# JTAG_Configuration.net
KiCad netlist of a schematic drawn in Altium Designer
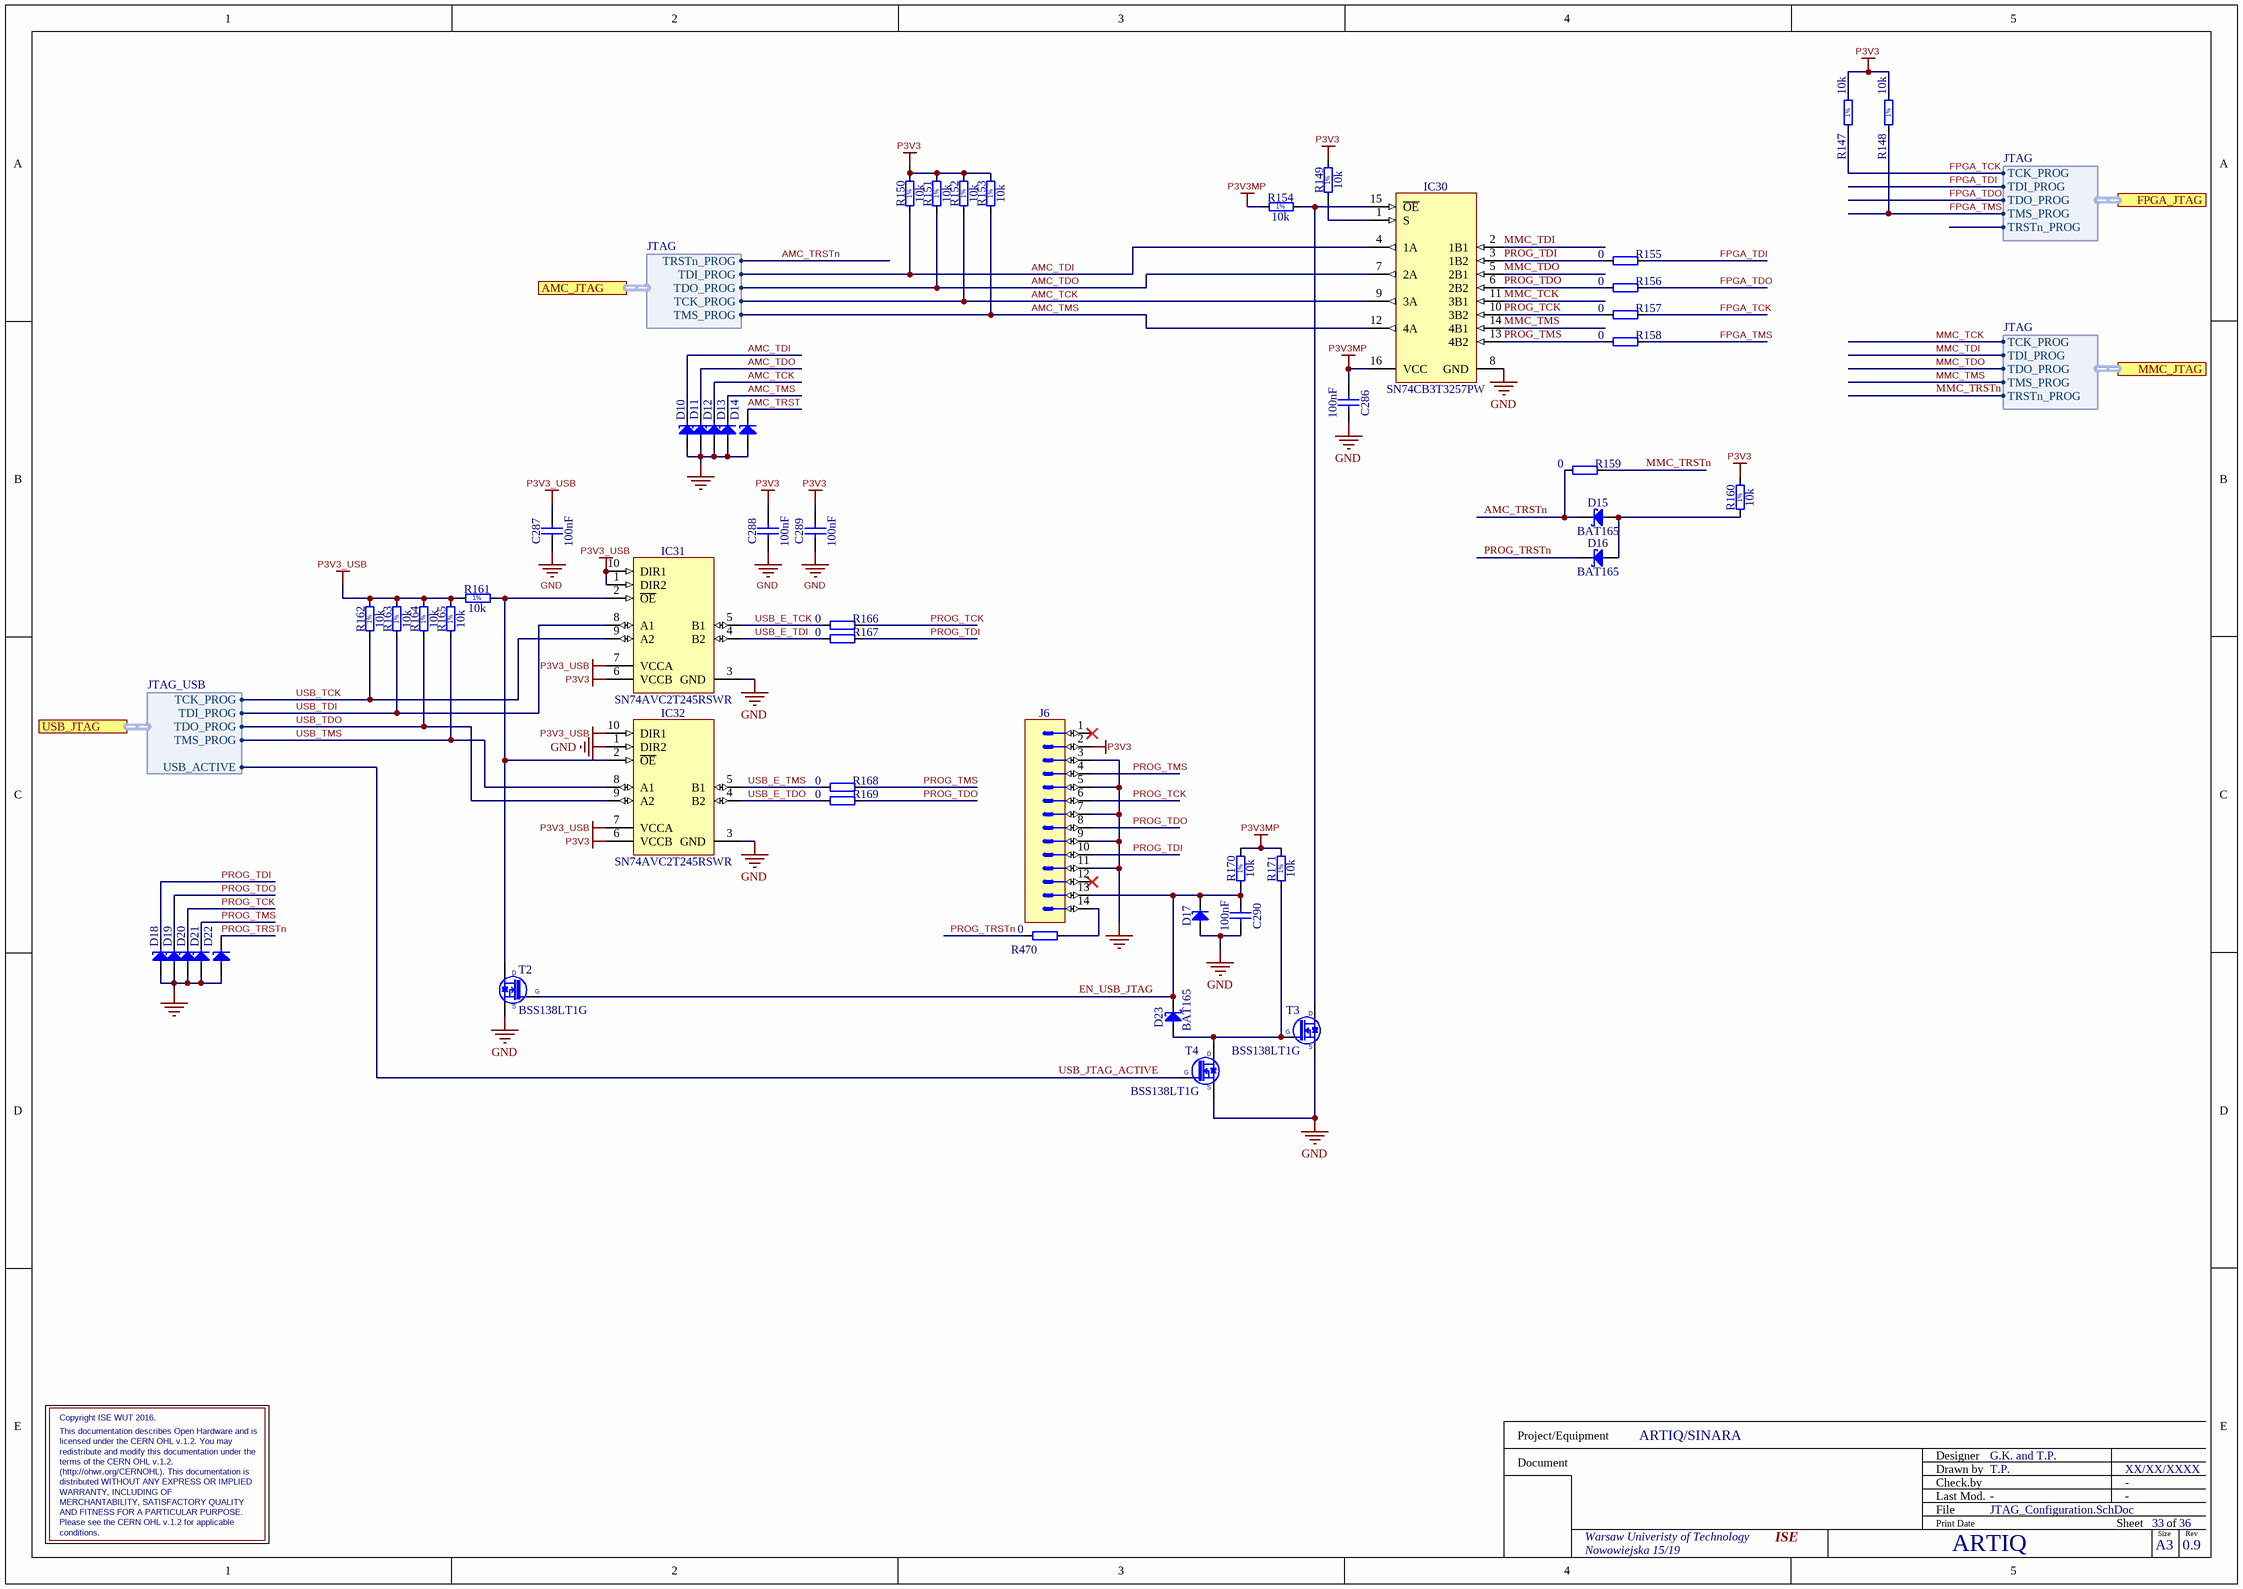
[diagram p0: JTAG_Configuration.SchDoc]

(export (version "E")
  (design (tool "Eeschema 10.0.6"))
  (components
    (comp (ref "C286")
      (value "100nF")
      (footprint "CAPC0603X33N")
      (description "Non-polarised capacitor")
      (fields
        (field (name "MANUFACTURER PART NUMBER") "CC0201_100NF_6.3V_10%_X5R")
        (field (name "MANUFACTURER") "GENERIC")
        (field (name "AUTHOR") "CERN DEM JLC")
      )
      (libsource (lib "Capacitors") (part "Capacitor - non polarized"))
    )
    (comp (ref "C287")
      (value "100nF")
      (footprint "CAPC0603X33N")
      (description "Non-polarised capacitor")
      (fields
        (field (name "MANUFACTURER PART NUMBER") "CC0201_100NF_6.3V_10%_X5R")
        (field (name "MANUFACTURER") "GENERIC")
        (field (name "AUTHOR") "CERN DEM JLC")
      )
      (libsource (lib "Capacitors") (part "Capacitor - non polarized"))
    )
    (comp (ref "C288")
      (value "100nF")
      (footprint "CAPC0603X33N")
      (description "Non-polarised capacitor")
      (fields
        (field (name "MANUFACTURER PART NUMBER") "CC0201_100NF_6.3V_10%_X5R")
        (field (name "MANUFACTURER") "GENERIC")
        (field (name "AUTHOR") "CERN DEM JLC")
      )
      (libsource (lib "Capacitors") (part "Capacitor - non polarized"))
    )
    (comp (ref "C289")
      (value "100nF")
      (footprint "CAPC0603X33N")
      (description "Non-polarised capacitor")
      (fields
        (field (name "MANUFACTURER PART NUMBER") "CC0201_100NF_6.3V_10%_X5R")
        (field (name "MANUFACTURER") "GENERIC")
        (field (name "AUTHOR") "CERN DEM JLC")
      )
      (libsource (lib "Capacitors") (part "Capacitor - non polarized"))
    )
    (comp (ref "C290")
      (value "100nF")
      (footprint "CAPC0603X33N")
      (description "Non-polarised capacitor")
      (fields
        (field (name "MANUFACTURER PART NUMBER") "CC0201_100NF_6.3V_10%_X5R")
        (field (name "MANUFACTURER") "GENERIC")
        (field (name "AUTHOR") "CERN DEM JLC")
      )
      (libsource (lib "Capacitors") (part "Capacitor - non polarized"))
    )
    (comp (ref "D10")
      (value "PESD3V3S1UB")
      (footprint "SODFL1608X65N")
      (description "ESD protection diode")
      (fields
        (field (name "MANUFACTURER") "NXP SEMICONDUCTORS")
        (field (name "VOLTAGE") "3V3")
        (field (name "AUTHOR") "CERN DEM JLC")
      )
      (libsource (lib "ICs And Semiconductors") (part "Diode ESD"))
    )
    (comp (ref "D11")
      (value "PESD3V3S1UB")
      (footprint "SODFL1608X65N")
      (description "ESD protection diode")
      (fields
        (field (name "MANUFACTURER") "NXP SEMICONDUCTORS")
        (field (name "VOLTAGE") "3V3")
        (field (name "AUTHOR") "CERN DEM JLC")
      )
      (libsource (lib "ICs And Semiconductors") (part "Diode ESD"))
    )
    (comp (ref "D12")
      (value "PESD3V3S1UB")
      (footprint "SODFL1608X65N")
      (description "ESD protection diode")
      (fields
        (field (name "MANUFACTURER") "NXP SEMICONDUCTORS")
        (field (name "VOLTAGE") "3V3")
        (field (name "AUTHOR") "CERN DEM JLC")
      )
      (libsource (lib "ICs And Semiconductors") (part "Diode ESD"))
    )
    (comp (ref "D13")
      (value "PESD3V3S1UB")
      (footprint "SODFL1608X65N")
      (description "ESD protection diode")
      (fields
        (field (name "MANUFACTURER") "NXP SEMICONDUCTORS")
        (field (name "VOLTAGE") "3V3")
        (field (name "AUTHOR") "CERN DEM JLC")
      )
      (libsource (lib "ICs And Semiconductors") (part "Diode ESD"))
    )
    (comp (ref "D14")
      (value "PESD3V3S1UB")
      (footprint "SODFL1608X65N")
      (description "ESD protection diode")
      (fields
        (field (name "MANUFACTURER") "NXP SEMICONDUCTORS")
        (field (name "VOLTAGE") "3V3")
        (field (name "AUTHOR") "CERN DEM JLC")
      )
      (libsource (lib "ICs And Semiconductors") (part "Diode ESD"))
    )
    (comp (ref "D15")
      (value "BAT165")
      (footprint "SOD2512X110N")
      (description "Schottky Diode")
      (fields
        (field (name "VOLTAGE") "40V")
        (field (name "POWER") "750mA")
        (field (name "AUTHOR") "CERN DEM JLC")
      )
      (libsource (lib "ICs And Semiconductors") (part "Diode Schottky"))
    )
    (comp (ref "D16")
      (value "BAT165")
      (footprint "SOD2512X110N")
      (description "Schottky Diode")
      (fields
        (field (name "VOLTAGE") "40V")
        (field (name "POWER") "750mA")
        (field (name "AUTHOR") "CERN DEM JLC")
      )
      (libsource (lib "ICs And Semiconductors") (part "Diode Schottky"))
    )
    (comp (ref "D17")
      (value "PESD3V3S1UB")
      (footprint "SODFL1608X65N")
      (description "ESD protection diode")
      (fields
        (field (name "VOLTAGE") "3V3")
        (field (name "POWER") "330W")
        (field (name "AUTHOR") "CERN DEM JLC")
      )
      (libsource (lib "ICs And Semiconductors") (part "Diode ESD"))
    )
    (comp (ref "D18")
      (value "PESD3V3S1UB")
      (footprint "SODFL1608X65N")
      (description "ESD protection diode")
      (fields
        (field (name "MANUFACTURER") "NXP SEMICONDUCTORS")
        (field (name "VOLTAGE") "3V3")
        (field (name "AUTHOR") "CERN DEM JLC")
      )
      (libsource (lib "ICs And Semiconductors") (part "Diode ESD"))
    )
    (comp (ref "D19")
      (value "PESD3V3S1UB")
      (footprint "SODFL1608X65N")
      (description "ESD protection diode")
      (fields
        (field (name "MANUFACTURER") "NXP SEMICONDUCTORS")
        (field (name "VOLTAGE") "3V3")
        (field (name "AUTHOR") "CERN DEM JLC")
      )
      (libsource (lib "ICs And Semiconductors") (part "Diode ESD"))
    )
    (comp (ref "D20")
      (value "PESD3V3S1UB")
      (footprint "SODFL1608X65N")
      (description "ESD protection diode")
      (fields
        (field (name "MANUFACTURER") "NXP SEMICONDUCTORS")
        (field (name "VOLTAGE") "3V3")
        (field (name "AUTHOR") "CERN DEM JLC")
      )
      (libsource (lib "ICs And Semiconductors") (part "Diode ESD"))
    )
    (comp (ref "D21")
      (value "PESD3V3S1UB")
      (footprint "SODFL1608X65N")
      (description "ESD protection diode")
      (fields
        (field (name "MANUFACTURER") "NXP SEMICONDUCTORS")
        (field (name "VOLTAGE") "3V3")
        (field (name "AUTHOR") "CERN DEM JLC")
      )
      (libsource (lib "ICs And Semiconductors") (part "Diode ESD"))
    )
    (comp (ref "D22")
      (value "PESD3V3S1UB")
      (footprint "SODFL1608X65N")
      (description "ESD protection diode")
      (fields
        (field (name "MANUFACTURER") "NXP SEMICONDUCTORS")
        (field (name "VOLTAGE") "3V3")
        (field (name "AUTHOR") "CERN DEM JLC")
      )
      (libsource (lib "ICs And Semiconductors") (part "Diode ESD"))
    )
    (comp (ref "D23")
      (value "BAT165")
      (footprint "SOD2512X110N")
      (description "Schottky Diode")
      (fields
        (field (name "VOLTAGE") "40V")
        (field (name "POWER") "750mA")
        (field (name "AUTHOR") "CERN DEM JLC")
      )
      (libsource (lib "ICs And Semiconductors") (part "Diode Schottky"))
    )
    (comp (ref "IC30")
      (value "SN74CB3T3257PW")
      (footprint "SOP65P640X120-16N")
      (description "4-BIT 1-OF-2 FET Multiplexer/Demultiplexer 2.5V/3.3V Low-Voltage Bus Switch 5V Tolerant Shifter")
      (fields (field (name "MANUFACTURER") "TEXAS INSTRUMENTS") (field (name "AUTHOR") "CERN DEM JLC"))
      (libsource (lib "ICs And Semiconductors") (part "743257"))
    )
    (comp (ref "IC31")
      (value "SN74AVC2T245RSWR")
      (footprint "QFN40P140X180X55-10N")
      (description "Dual-Bit Dual-Supply Bus Transceiver With Configurable Voltage Translation and 3-State Outputs")
      (fields (field (name "MANUFACTURER") "TEXAS INSTRUMENTS") (field (name "AUTHOR") "CERN DEM JLC"))
      (libsource (lib "ICs And Semiconductors") (part "742T245"))
    )
    (comp (ref "IC32")
      (value "SN74AVC2T245RSWR")
      (footprint "QFN40P140X180X55-10N")
      (description "Dual-Bit Dual-Supply Bus Transceiver With Configurable Voltage Translation and 3-State Outputs")
      (fields (field (name "MANUFACTURER") "TEXAS INSTRUMENTS") (field (name "AUTHOR") "CERN DEM JLC"))
      (libsource (lib "ICs And Semiconductors") (part "742T245"))
    )
    (comp (ref "J6")
      (value "Milli-Grid™")
      (footprint "MOLEX_87832-1420")
      (description "Connector 14 Male")
      (fields
        (field (name "MANUFACTURER PART NUMBER") "87832-1420")
        (field (name "MANUFACTURER") "MOLEX")
        (field (name "AUTHOR") "CERN DEM JLC")
      )
      (libsource (lib "Connectors") (part "Connector 14 Male"))
    )
    (comp (ref "R147")
      (value "10k")
      (footprint "RESC1005X40N")
      (description "Resistor - 1%")
      (fields
        (field (name "MANUFACTURER PART NUMBER") "R0402_10K_1%_0.0625W_100PPM")
        (field (name "MANUFACTURER") "GENERIC")
        (field (name "AUTHOR") "CERN DEM JLC")
      )
      (libsource (lib "Resistors") (part "Resistor - 1%"))
    )
    (comp (ref "R148")
      (value "10k")
      (footprint "RESC1005X40N")
      (description "Resistor - 1%")
      (fields
        (field (name "MANUFACTURER PART NUMBER") "R0402_10K_1%_0.0625W_100PPM")
        (field (name "MANUFACTURER") "GENERIC")
        (field (name "AUTHOR") "CERN DEM JLC")
      )
      (libsource (lib "Resistors") (part "Resistor - 1%"))
    )
    (comp (ref "R149")
      (value "10k")
      (footprint "RESC1005X40N")
      (description "Resistor - 1%")
      (fields
        (field (name "MANUFACTURER PART NUMBER") "R0402_10K_1%_0.0625W_100PPM")
        (field (name "MANUFACTURER") "GENERIC")
        (field (name "AUTHOR") "CERN DEM JLC")
      )
      (libsource (lib "Resistors") (part "Resistor - 1%"))
    )
    (comp (ref "R150")
      (value "10k")
      (footprint "RESC1005X40N")
      (description "Resistor - 1%")
      (fields
        (field (name "MANUFACTURER PART NUMBER") "R0402_10K_1%_0.0625W_100PPM")
        (field (name "MANUFACTURER") "GENERIC")
        (field (name "AUTHOR") "CERN DEM JLC")
      )
      (libsource (lib "Resistors") (part "Resistor - 1%"))
    )
    (comp (ref "R151")
      (value "10k")
      (footprint "RESC1005X40N")
      (description "Resistor - 1%")
      (fields
        (field (name "MANUFACTURER PART NUMBER") "R0402_10K_1%_0.0625W_100PPM")
        (field (name "MANUFACTURER") "GENERIC")
        (field (name "AUTHOR") "CERN DEM JLC")
      )
      (libsource (lib "Resistors") (part "Resistor - 1%"))
    )
    (comp (ref "R152")
      (value "10k")
      (footprint "RESC1005X40N")
      (description "Resistor - 1%")
      (fields
        (field (name "MANUFACTURER PART NUMBER") "R0402_10K_1%_0.0625W_100PPM")
        (field (name "MANUFACTURER") "GENERIC")
        (field (name "AUTHOR") "CERN DEM JLC")
      )
      (libsource (lib "Resistors") (part "Resistor - 1%"))
    )
    (comp (ref "R153")
      (value "10k")
      (footprint "RESC1005X40N")
      (description "Resistor - 1%")
      (fields
        (field (name "MANUFACTURER PART NUMBER") "R0402_10K_1%_0.0625W_100PPM")
        (field (name "MANUFACTURER") "GENERIC")
        (field (name "AUTHOR") "CERN DEM JLC")
      )
      (libsource (lib "Resistors") (part "Resistor - 1%"))
    )
    (comp (ref "R154")
      (value "10k")
      (footprint "RESC1005X40N")
      (description "Resistor - 1%")
      (fields
        (field (name "MANUFACTURER PART NUMBER") "R0402_10K_1%_0.0625W_100PPM")
        (field (name "MANUFACTURER") "GENERIC")
        (field (name "AUTHOR") "CERN DEM JLC")
      )
      (libsource (lib "Resistors") (part "Resistor - 1%"))
    )
    (comp (ref "R155")
      (value "0")
      (footprint "RESC1005X40N")
      (description "Resistor")
      (fields
        (field (name "MANUFACTURER PART NUMBER") "R0402_0R_JUMPER")
        (field (name "MANUFACTURER") "GENERIC")
        (field (name "AUTHOR") "CERN DEM JLC")
      )
      (libsource (lib "Resistors") (part "Resistor"))
    )
    (comp (ref "R156")
      (value "0")
      (footprint "RESC1005X40N")
      (description "Resistor")
      (fields
        (field (name "MANUFACTURER PART NUMBER") "R0402_0R_JUMPER")
        (field (name "MANUFACTURER") "GENERIC")
        (field (name "AUTHOR") "CERN DEM JLC")
      )
      (libsource (lib "Resistors") (part "Resistor"))
    )
    (comp (ref "R157")
      (value "0")
      (footprint "RESC1005X40N")
      (description "Resistor")
      (fields
        (field (name "MANUFACTURER PART NUMBER") "R0402_0R_JUMPER")
        (field (name "MANUFACTURER") "GENERIC")
        (field (name "AUTHOR") "CERN DEM JLC")
      )
      (libsource (lib "Resistors") (part "Resistor"))
    )
    (comp (ref "R158")
      (value "0")
      (footprint "RESC1005X40N")
      (description "Resistor")
      (fields
        (field (name "MANUFACTURER PART NUMBER") "R0402_0R_JUMPER")
        (field (name "MANUFACTURER") "GENERIC")
        (field (name "AUTHOR") "CERN DEM JLC")
      )
      (libsource (lib "Resistors") (part "Resistor"))
    )
    (comp (ref "R159")
      (value "0")
      (footprint "RESC1005X40N")
      (description "Resistor")
      (fields
        (field (name "MANUFACTURER PART NUMBER") "R0402_0R_JUMPER")
        (field (name "MANUFACTURER") "GENERIC")
        (field (name "AUTHOR") "CERN DEM JLC")
      )
      (libsource (lib "Resistors") (part "Resistor"))
    )
    (comp (ref "R160")
      (value "10k")
      (footprint "RESC1005X40N")
      (description "Resistor - 1%")
      (fields
        (field (name "MANUFACTURER PART NUMBER") "R0402_10K_1%_0.0625W_100PPM")
        (field (name "MANUFACTURER") "GENERIC")
        (field (name "AUTHOR") "CERN DEM JLC")
      )
      (libsource (lib "Resistors") (part "Resistor - 1%"))
    )
    (comp (ref "R161")
      (value "10k")
      (footprint "RESC1005X40N")
      (description "Resistor - 1%")
      (fields
        (field (name "PART NUMBER") "R0402_10K_1%_0.0625W_100PPM")
        (field (name "POWER") "0.0625W")
        (field (name "AUTHOR") "CERN DEM JLC")
      )
      (libsource (lib "Resistors") (part "Resistor - 1%"))
    )
    (comp (ref "R162")
      (value "10k")
      (footprint "RESC1005X40N")
      (description "Resistor - 1%")
      (fields
        (field (name "MANUFACTURER PART NUMBER") "R0402_10K_1%_0.0625W_100PPM")
        (field (name "MANUFACTURER") "GENERIC")
        (field (name "AUTHOR") "CERN DEM JLC")
      )
      (libsource (lib "Resistors") (part "Resistor - 1%"))
    )
    (comp (ref "R163")
      (value "10k")
      (footprint "RESC1005X40N")
      (description "Resistor - 1%")
      (fields
        (field (name "MANUFACTURER PART NUMBER") "R0402_10K_1%_0.0625W_100PPM")
        (field (name "MANUFACTURER") "GENERIC")
        (field (name "AUTHOR") "CERN DEM JLC")
      )
      (libsource (lib "Resistors") (part "Resistor - 1%"))
    )
    (comp (ref "R164")
      (value "10k")
      (footprint "RESC1005X40N")
      (description "Resistor - 1%")
      (fields
        (field (name "MANUFACTURER PART NUMBER") "R0402_10K_1%_0.0625W_100PPM")
        (field (name "MANUFACTURER") "GENERIC")
        (field (name "AUTHOR") "CERN DEM JLC")
      )
      (libsource (lib "Resistors") (part "Resistor - 1%"))
    )
    (comp (ref "R165")
      (value "10k")
      (footprint "RESC1005X40N")
      (description "Resistor - 1%")
      (fields
        (field (name "MANUFACTURER PART NUMBER") "R0402_10K_1%_0.0625W_100PPM")
        (field (name "MANUFACTURER") "GENERIC")
        (field (name "AUTHOR") "CERN DEM JLC")
      )
      (libsource (lib "Resistors") (part "Resistor - 1%"))
    )
    (comp (ref "R166")
      (value "0")
      (footprint "RESC1005X40N")
      (description "Resistor")
      (fields
        (field (name "MANUFACTURER PART NUMBER") "R0402_0R_JUMPER")
        (field (name "MANUFACTURER") "GENERIC")
        (field (name "AUTHOR") "CERN DEM JLC")
      )
      (libsource (lib "Resistors") (part "Resistor"))
    )
    (comp (ref "R167")
      (value "0")
      (footprint "RESC1005X40N")
      (description "Resistor")
      (fields
        (field (name "MANUFACTURER PART NUMBER") "R0402_0R_JUMPER")
        (field (name "MANUFACTURER") "GENERIC")
        (field (name "AUTHOR") "CERN DEM JLC")
      )
      (libsource (lib "Resistors") (part "Resistor"))
    )
    (comp (ref "R168")
      (value "0")
      (footprint "RESC1005X40N")
      (description "Resistor")
      (fields
        (field (name "MANUFACTURER PART NUMBER") "R0402_0R_JUMPER")
        (field (name "MANUFACTURER") "GENERIC")
        (field (name "AUTHOR") "CERN DEM JLC")
      )
      (libsource (lib "Resistors") (part "Resistor"))
    )
    (comp (ref "R169")
      (value "0")
      (footprint "RESC1005X40N")
      (description "Resistor")
      (fields
        (field (name "MANUFACTURER PART NUMBER") "R0402_0R_JUMPER")
        (field (name "MANUFACTURER") "GENERIC")
        (field (name "AUTHOR") "CERN DEM JLC")
      )
      (libsource (lib "Resistors") (part "Resistor"))
    )
    (comp (ref "R170")
      (value "10k")
      (footprint "RESC1005X40N")
      (description "Resistor - 1%")
      (fields
        (field (name "MANUFACTURER PART NUMBER") "R0402_10K_1%_0.0625W_100PPM")
        (field (name "MANUFACTURER") "GENERIC")
        (field (name "AUTHOR") "CERN DEM JLC")
      )
      (libsource (lib "Resistors") (part "Resistor - 1%"))
    )
    (comp (ref "R171")
      (value "10k")
      (footprint "RESC1005X40N")
      (description "Resistor - 1%")
      (fields
        (field (name "MANUFACTURER PART NUMBER") "R0402_10K_1%_0.0625W_100PPM")
        (field (name "MANUFACTURER") "GENERIC")
        (field (name "AUTHOR") "CERN DEM JLC")
      )
      (libsource (lib "Resistors") (part "Resistor - 1%"))
    )
    (comp (ref "R470")
      (value "0")
      (footprint "RESC1005X40N")
      (description "Resistor")
      (fields
        (field (name "MANUFACTURER PART NUMBER") "R0402_0R_JUMPER")
        (field (name "MANUFACTURER") "GENERIC")
        (field (name "AUTHOR") "CERN DEM JLC")
      )
      (libsource (lib "Resistors") (part "Resistor"))
    )
    (comp (ref "T2")
      (value "BSS138LT1G")
      (footprint "SOT95P240X110-3N")
      (description "N-CHANNEL MOSFET WITH DIODE")
      (fields (field (name "MANUFACTURER") "ON SEMICONDUCTOR") (field (name "AUTHOR") "CERN DEM JLC"))
      (libsource (lib "ICs And Semiconductors") (part "N-MOSFET-D 1G 2S 3D"))
    )
    (comp (ref "T3")
      (value "BSS138LT1G")
      (footprint "SOT95P240X110-3N")
      (description "N-CHANNEL MOSFET WITH DIODE")
      (fields (field (name "MANUFACTURER") "ON SEMICONDUCTOR") (field (name "AUTHOR") "CERN DEM JLC"))
      (libsource (lib "") (part "N-MOSFET-D 1G 2S 3D_1"))
    )
    (comp (ref "T4")
      (value "BSS138LT1G")
      (footprint "SOT95P240X110-3N")
      (description "N-CHANNEL MOSFET WITH DIODE")
      (fields (field (name "MANUFACTURER") "ON SEMICONDUCTOR") (field (name "AUTHOR") "CERN DEM JLC"))
      (libsource (lib "") (part "N-MOSFET-D 1G 2S 3D_1"))
    )
  )
  (nets
    (net (code "3") (name "/AMC_TCK") (class "Default")
      (node (ref "D12") (pin "1") (pinfunction "C_1") (pintype "passive"))
      (node (ref "IC30") (pin "9") (pinfunction "3A_9") (pintype "output"))
      (node (ref "R152") (pin "1") (pinfunction "1_1") (pintype "passive"))
    )
    (net (code "4") (name "/AMC_TDI") (class "Default")
      (node (ref "D10") (pin "1") (pinfunction "C_1") (pintype "passive"))
      (node (ref "IC30") (pin "4") (pinfunction "1A_4") (pintype "output"))
      (node (ref "R150") (pin "1") (pinfunction "1_1") (pintype "passive"))
    )
    (net (code "5") (name "/AMC_TDO") (class "Default")
      (node (ref "D11") (pin "1") (pinfunction "C_1") (pintype "passive"))
      (node (ref "IC30") (pin "7") (pinfunction "2A_7") (pintype "output"))
      (node (ref "R151") (pin "1") (pinfunction "1_1") (pintype "passive"))
    )
    (net (code "6") (name "/AMC_TMS") (class "Default")
      (node (ref "D13") (pin "1") (pinfunction "C_1") (pintype "passive"))
      (node (ref "IC30") (pin "12") (pinfunction "4A_12") (pintype "output"))
      (node (ref "R153") (pin "1") (pinfunction "1_1") (pintype "passive"))
    )
    (net (code "7") (name "/AMC_TRST") (class "Default")
      (node (ref "D14") (pin "1") (pinfunction "C_1") (pintype "passive"))
    )
    (net (code "8") (name "/AMC_TRSTn") (class "Default")
      (node (ref "D15") (pin "1") (pinfunction "C_1") (pintype "passive"))
      (node (ref "R159") (pin "2") (pinfunction "2_2") (pintype "passive"))
    )
    (net (code "9") (name "/EN_USB_JTAG") (class "Default")
      (node (ref "C290") (pin "2") (pinfunction "2_2") (pintype "passive"))
      (node (ref "D17") (pin "1") (pinfunction "C_1") (pintype "passive"))
      (node (ref "D23") (pin "1") (pinfunction "C_1") (pintype "passive"))
      (node (ref "J6") (pin "13") (pinfunction "13_13") (pintype "bidirectional"))
      (node (ref "R170") (pin "1") (pinfunction "1_1") (pintype "passive"))
      (node (ref "T2") (pin "1") (pinfunction "G_1") (pintype "passive"))
    )
    (net (code "10") (name "/FPGA_TCK") (class "Default")
      (node (ref "R147") (pin "2") (pinfunction "2_2") (pintype "passive"))
      (node (ref "R157") (pin "1") (pinfunction "1_1") (pintype "passive"))
    )
    (net (code "11") (name "/FPGA_TDI") (class "Default")
      (node (ref "R155") (pin "1") (pinfunction "1_1") (pintype "passive"))
    )
    (net (code "12") (name "/FPGA_TDO") (class "Default")
      (node (ref "R156") (pin "1") (pinfunction "1_1") (pintype "passive"))
    )
    (net (code "13") (name "/FPGA_TMS") (class "Default")
      (node (ref "R148") (pin "2") (pinfunction "2_2") (pintype "passive"))
      (node (ref "R158") (pin "1") (pinfunction "1_1") (pintype "passive"))
    )
    (net (code "14") (name "/MMC_TCK") (class "Default")
      (node (ref "IC30") (pin "11") (pinfunction "3B1_11") (pintype "input"))
    )
    (net (code "15") (name "/MMC_TDI") (class "Default")
      (node (ref "IC30") (pin "2") (pinfunction "1B1_2") (pintype "input"))
    )
    (net (code "16") (name "/MMC_TDO") (class "Default")
      (node (ref "IC30") (pin "5") (pinfunction "2B1_5") (pintype "input"))
    )
    (net (code "17") (name "/MMC_TMS") (class "Default")
      (node (ref "IC30") (pin "14") (pinfunction "4B1_14") (pintype "input"))
    )
    (net (code "18") (name "/MMC_TRSTn") (class "Default")
      (node (ref "R159") (pin "1") (pinfunction "1_1") (pintype "passive"))
    )
    (net (code "19") (name "/PROG_TCK") (class "Default")
      (node (ref "D20") (pin "1") (pinfunction "C_1") (pintype "passive"))
      (node (ref "IC30") (pin "10") (pinfunction "3B2_10") (pintype "input"))
      (node (ref "J6") (pin "6") (pinfunction "6_6") (pintype "bidirectional"))
      (node (ref "R157") (pin "2") (pinfunction "2_2") (pintype "passive"))
      (node (ref "R166") (pin "1") (pinfunction "1_1") (pintype "passive"))
    )
    (net (code "20") (name "/PROG_TDI") (class "Default")
      (node (ref "D18") (pin "1") (pinfunction "C_1") (pintype "passive"))
      (node (ref "IC30") (pin "3") (pinfunction "1B2_3") (pintype "input"))
      (node (ref "J6") (pin "10") (pinfunction "10_10") (pintype "bidirectional"))
      (node (ref "R155") (pin "2") (pinfunction "2_2") (pintype "passive"))
      (node (ref "R167") (pin "1") (pinfunction "1_1") (pintype "passive"))
    )
    (net (code "21") (name "/PROG_TDO") (class "Default")
      (node (ref "D19") (pin "1") (pinfunction "C_1") (pintype "passive"))
      (node (ref "IC30") (pin "6") (pinfunction "2B2_6") (pintype "input"))
      (node (ref "J6") (pin "8") (pinfunction "8_8") (pintype "bidirectional"))
      (node (ref "R156") (pin "2") (pinfunction "2_2") (pintype "passive"))
      (node (ref "R169") (pin "1") (pinfunction "1_1") (pintype "passive"))
    )
    (net (code "22") (name "/PROG_TMS") (class "Default")
      (node (ref "D21") (pin "1") (pinfunction "C_1") (pintype "passive"))
      (node (ref "IC30") (pin "13") (pinfunction "4B2_13") (pintype "input"))
      (node (ref "J6") (pin "4") (pinfunction "4_4") (pintype "bidirectional"))
      (node (ref "R158") (pin "2") (pinfunction "2_2") (pintype "passive"))
      (node (ref "R168") (pin "1") (pinfunction "1_1") (pintype "passive"))
    )
    (net (code "23") (name "/PROG_TRSTn") (class "Default")
      (node (ref "D16") (pin "1") (pinfunction "C_1") (pintype "passive"))
      (node (ref "D22") (pin "1") (pinfunction "C_1") (pintype "passive"))
      (node (ref "R470") (pin "2") (pinfunction "2_2") (pintype "passive"))
    )
    (net (code "24") (name "/USB_E_TCK") (class "Default")
      (node (ref "IC31") (pin "5") (pinfunction "B1_5") (pintype "bidirectional"))
      (node (ref "R166") (pin "2") (pinfunction "2_2") (pintype "passive"))
    )
    (net (code "25") (name "/USB_E_TDI") (class "Default")
      (node (ref "IC31") (pin "4") (pinfunction "B2_4") (pintype "bidirectional"))
      (node (ref "R167") (pin "2") (pinfunction "2_2") (pintype "passive"))
    )
    (net (code "26") (name "/USB_E_TDO") (class "Default")
      (node (ref "IC32") (pin "4") (pinfunction "B2_4") (pintype "bidirectional"))
      (node (ref "R169") (pin "2") (pinfunction "2_2") (pintype "passive"))
    )
    (net (code "27") (name "/USB_E_TMS") (class "Default")
      (node (ref "IC32") (pin "5") (pinfunction "B1_5") (pintype "bidirectional"))
      (node (ref "R168") (pin "2") (pinfunction "2_2") (pintype "passive"))
    )
    (net (code "28") (name "/USB_JTAG_ACTIVE") (class "Default")
      (node (ref "T4") (pin "1") (pinfunction "G_1") (pintype "passive"))
    )
    (net (code "29") (name "/USB_TCK") (class "Default")
      (node (ref "IC31") (pin "9") (pinfunction "A2_9") (pintype "bidirectional"))
      (node (ref "R162") (pin "1") (pinfunction "1_1") (pintype "passive"))
    )
    (net (code "30") (name "/USB_TDI") (class "Default")
      (node (ref "IC31") (pin "8") (pinfunction "A1_8") (pintype "bidirectional"))
      (node (ref "R163") (pin "1") (pinfunction "1_1") (pintype "passive"))
    )
    (net (code "31") (name "/USB_TDO") (class "Default")
      (node (ref "IC32") (pin "9") (pinfunction "A2_9") (pintype "bidirectional"))
      (node (ref "R164") (pin "1") (pinfunction "1_1") (pintype "passive"))
    )
    (net (code "32") (name "/USB_TMS") (class "Default")
      (node (ref "IC32") (pin "8") (pinfunction "A1_8") (pintype "bidirectional"))
      (node (ref "R165") (pin "1") (pinfunction "1_1") (pintype "passive"))
    )
    (net (code "35") (name "GND") (class "Default")
      (node (ref "C286") (pin "1") (pinfunction "1_1") (pintype "passive"))
      (node (ref "C287") (pin "1") (pinfunction "1_1") (pintype "passive"))
      (node (ref "C288") (pin "1") (pinfunction "1_1") (pintype "passive"))
      (node (ref "C289") (pin "1") (pinfunction "1_1") (pintype "passive"))
      (node (ref "C290") (pin "1") (pinfunction "1_1") (pintype "passive"))
      (node (ref "D10") (pin "2") (pinfunction "A_2") (pintype "passive"))
      (node (ref "D11") (pin "2") (pinfunction "A_2") (pintype "passive"))
      (node (ref "D12") (pin "2") (pinfunction "A_2") (pintype "passive"))
      (node (ref "D13") (pin "2") (pinfunction "A_2") (pintype "passive"))
      (node (ref "D14") (pin "2") (pinfunction "A_2") (pintype "passive"))
      (node (ref "D17") (pin "2") (pinfunction "A_2") (pintype "passive"))
      (node (ref "D18") (pin "2") (pinfunction "A_2") (pintype "passive"))
      (node (ref "D19") (pin "2") (pinfunction "A_2") (pintype "passive"))
      (node (ref "D20") (pin "2") (pinfunction "A_2") (pintype "passive"))
      (node (ref "D21") (pin "2") (pinfunction "A_2") (pintype "passive"))
      (node (ref "D22") (pin "2") (pinfunction "A_2") (pintype "passive"))
      (node (ref "IC30") (pin "8") (pinfunction "GND_8") (pintype "power_in"))
      (node (ref "IC31") (pin "3") (pinfunction "GND_3") (pintype "power_in"))
      (node (ref "IC32") (pin "1") (pinfunction "DIR2_1") (pintype "input"))
      (node (ref "IC32") (pin "3") (pinfunction "GND_3") (pintype "power_in"))
      (node (ref "J6") (pin "11") (pinfunction "11_11") (pintype "bidirectional"))
      (node (ref "J6") (pin "3") (pinfunction "3_3") (pintype "bidirectional"))
      (node (ref "J6") (pin "5") (pinfunction "5_5") (pintype "bidirectional"))
      (node (ref "J6") (pin "7") (pinfunction "7_7") (pintype "bidirectional"))
      (node (ref "J6") (pin "9") (pinfunction "9_9") (pintype "bidirectional"))
      (node (ref "T2") (pin "2") (pinfunction "S_2") (pintype "passive"))
      (node (ref "T3") (pin "2") (pinfunction "S_2") (pintype "passive"))
      (node (ref "T4") (pin "2") (pinfunction "S_2") (pintype "passive"))
    )
    (net (code "36") (name "Net-(D15-A)") (class "Default")
      (node (ref "D15") (pin "2") (pinfunction "A_2") (pintype "passive"))
      (node (ref "D16") (pin "2") (pinfunction "A_2") (pintype "passive"))
      (node (ref "R160") (pin "1") (pinfunction "1_1") (pintype "passive"))
    )
    (net (code "37") (name "Net-(D23-A)") (class "Default")
      (node (ref "D23") (pin "2") (pinfunction "A_2") (pintype "passive"))
      (node (ref "R171") (pin "1") (pinfunction "1_1") (pintype "passive"))
      (node (ref "T3") (pin "1") (pinfunction "G_1") (pintype "passive"))
      (node (ref "T4") (pin "3") (pinfunction "D_3") (pintype "passive"))
    )
    (net (code "38") (name "Net-(IC30-S)") (class "Default")
      (node (ref "IC30") (pin "1") (pinfunction "S_1") (pintype "input"))
      (node (ref "R149") (pin "1") (pinfunction "1_1") (pintype "passive"))
    )
    (net (code "39") (name "Net-(IC30-~{OE})") (class "Default")
      (node (ref "IC30") (pin "15") (pinfunction "~{OE}_15") (pintype "input"))
      (node (ref "R154") (pin "2") (pinfunction "2_2") (pintype "passive"))
      (node (ref "T3") (pin "3") (pinfunction "D_3") (pintype "passive"))
    )
    (net (code "40") (name "Net-(IC31-~{OE})") (class "Default")
      (node (ref "IC31") (pin "2") (pinfunction "~{OE}_2") (pintype "input"))
      (node (ref "IC32") (pin "2") (pinfunction "~{OE}_2") (pintype "input"))
      (node (ref "R161") (pin "2") (pinfunction "2_2") (pintype "passive"))
      (node (ref "T2") (pin "3") (pinfunction "D_3") (pintype "passive"))
    )
    (net (code "41") (name "Net-(J6-Pad14)") (class "Default")
      (node (ref "J6") (pin "14") (pinfunction "14_14") (pintype "bidirectional"))
      (node (ref "R470") (pin "1") (pinfunction "1_1") (pintype "passive"))
    )
    (net (code "42") (name "P3V3") (class "Default")
      (node (ref "C288") (pin "2") (pinfunction "2_2") (pintype "passive"))
      (node (ref "C289") (pin "2") (pinfunction "2_2") (pintype "passive"))
      (node (ref "IC31") (pin "6") (pinfunction "VCCB_6") (pintype "power_in"))
      (node (ref "IC32") (pin "6") (pinfunction "VCCB_6") (pintype "power_in"))
      (node (ref "J6") (pin "2") (pinfunction "2_2") (pintype "bidirectional"))
      (node (ref "R147") (pin "1") (pinfunction "1_1") (pintype "passive"))
      (node (ref "R148") (pin "1") (pinfunction "1_1") (pintype "passive"))
      (node (ref "R149") (pin "2") (pinfunction "2_2") (pintype "passive"))
      (node (ref "R150") (pin "2") (pinfunction "2_2") (pintype "passive"))
      (node (ref "R151") (pin "2") (pinfunction "2_2") (pintype "passive"))
      (node (ref "R152") (pin "2") (pinfunction "2_2") (pintype "passive"))
      (node (ref "R153") (pin "2") (pinfunction "2_2") (pintype "passive"))
      (node (ref "R160") (pin "2") (pinfunction "2_2") (pintype "passive"))
    )
    (net (code "43") (name "P3V3MP") (class "Default")
      (node (ref "C286") (pin "2") (pinfunction "2_2") (pintype "passive"))
      (node (ref "IC30") (pin "16") (pinfunction "VCC_16") (pintype "power_in"))
      (node (ref "R154") (pin "1") (pinfunction "1_1") (pintype "passive"))
      (node (ref "R170") (pin "2") (pinfunction "2_2") (pintype "passive"))
      (node (ref "R171") (pin "2") (pinfunction "2_2") (pintype "passive"))
    )
    (net (code "44") (name "P3V3_USB") (class "Default")
      (node (ref "C287") (pin "2") (pinfunction "2_2") (pintype "passive"))
      (node (ref "IC31") (pin "1") (pinfunction "DIR2_1") (pintype "input"))
      (node (ref "IC31") (pin "10") (pinfunction "DIR1_10") (pintype "input"))
      (node (ref "IC31") (pin "7") (pinfunction "VCCA_7") (pintype "power_in"))
      (node (ref "IC32") (pin "10") (pinfunction "DIR1_10") (pintype "input"))
      (node (ref "IC32") (pin "7") (pinfunction "VCCA_7") (pintype "power_in"))
      (node (ref "R161") (pin "1") (pinfunction "1_1") (pintype "passive"))
      (node (ref "R162") (pin "2") (pinfunction "2_2") (pintype "passive"))
      (node (ref "R163") (pin "2") (pinfunction "2_2") (pintype "passive"))
      (node (ref "R164") (pin "2") (pinfunction "2_2") (pintype "passive"))
      (node (ref "R165") (pin "2") (pinfunction "2_2") (pintype "passive"))
    )
    (net (code "45") (name "unconnected-(J6-Pad1)") (class "Default")
      (node (ref "J6") (pin "1") (pinfunction "1_1") (pintype "bidirectional+no_connect"))
    )
    (net (code "46") (name "unconnected-(J6-Pad12)") (class "Default")
      (node (ref "J6") (pin "12") (pinfunction "12_12") (pintype "bidirectional+no_connect"))
    )
  )
)
